# K-Diag_small-_single_small-multi.net
KiCad netlist of a schematic drawn in EAGLE
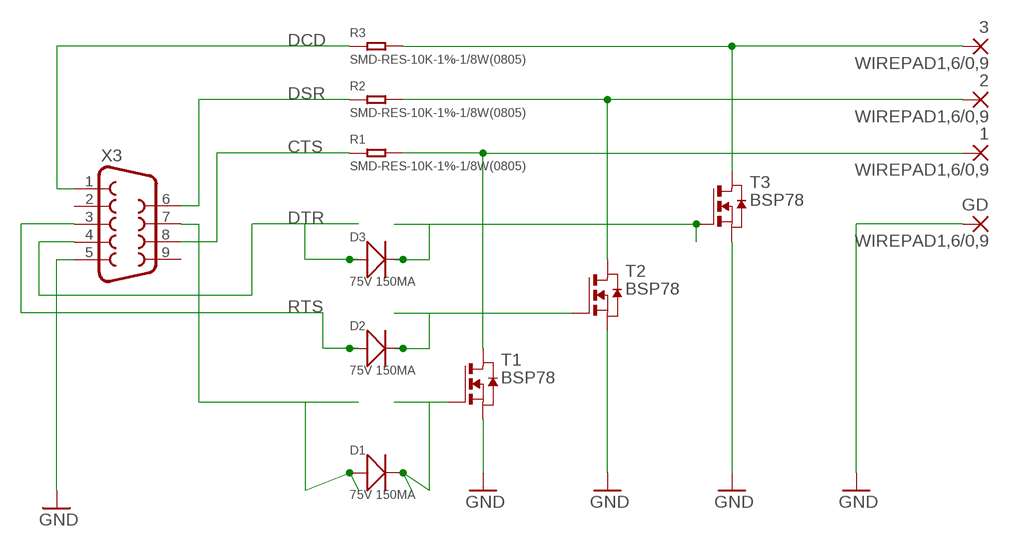
[diagram p0: schematic, sheet 1]
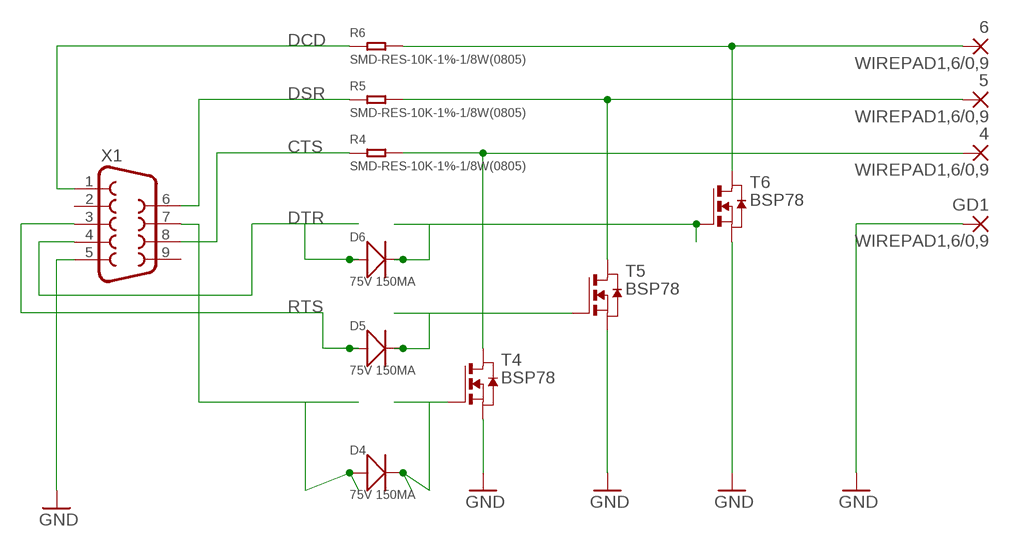
[diagram p1: schematic, sheet 2]
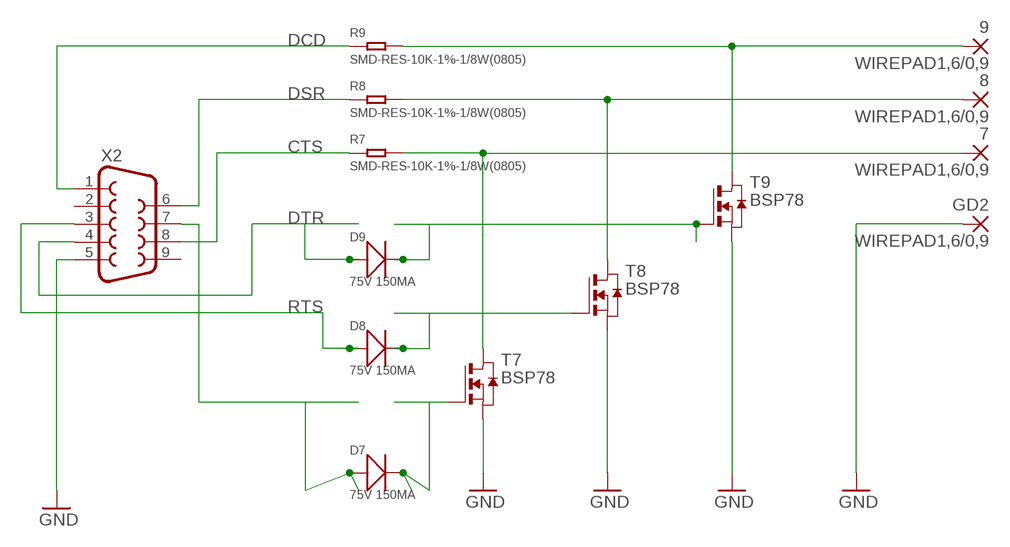
[diagram p2: schematic, sheet 3]

(export (version "E")
  (design (tool "Eeschema 10.0.6"))
  (components
    (comp (ref "7")
      (value "WIREPAD1,6/0,9")
      (footprint "eagle-import:1,6_0,9")
      (libsource (lib "eagle-import") (part "WIREPAD1,6/0,9"))
    )
    (comp (ref "8")
      (value "WIREPAD1,6/0,9")
      (footprint "eagle-import:1,6_0,9")
      (libsource (lib "eagle-import") (part "WIREPAD1,6/0,9"))
    )
    (comp (ref "9")
      (value "WIREPAD1,6/0,9")
      (footprint "eagle-import:1,6_0,9")
      (libsource (lib "eagle-import") (part "WIREPAD1,6/0,9"))
    )
    (comp (ref "D7")
      (value "75V 150MA")
      (footprint "eagle-import:LED-1206")
      (fields (field (name "MPN") "CD1206-S01575"))
      (libsource (lib "eagle-import") (part "SMD-DIODE-SWITCHING-75V-150MA(D1206)"))
    )
    (comp (ref "D8")
      (value "75V 150MA")
      (footprint "eagle-import:LED-1206")
      (fields (field (name "MPN") "CD1206-S01575"))
      (libsource (lib "eagle-import") (part "SMD-DIODE-SWITCHING-75V-150MA(D1206)"))
    )
    (comp (ref "D9")
      (value "75V 150MA")
      (footprint "eagle-import:LED-1206")
      (fields (field (name "MPN") "CD1206-S01575"))
      (libsource (lib "eagle-import") (part "SMD-DIODE-SWITCHING-75V-150MA(D1206)"))
    )
    (comp (ref "GD2")
      (value "WIREPAD1,6/0,9")
      (footprint "eagle-import:1,6_0,9")
      (libsource (lib "eagle-import") (part "WIREPAD1,6/0,9"))
    )
    (comp (ref "R7")
      (value "SMD-RES-10K-1%-1/8W(0805)")
      (footprint "eagle-import:R0805")
      (fields (field (name "MPN") "RC0805FR-0710KL"))
      (libsource (lib "eagle-import") (part "SMD-RES-10K-1%-1/8W(0805)"))
    )
    (comp (ref "R8")
      (value "SMD-RES-10K-1%-1/8W(0805)")
      (footprint "eagle-import:R0805")
      (fields (field (name "MPN") "RC0805FR-0710KL"))
      (libsource (lib "eagle-import") (part "SMD-RES-10K-1%-1/8W(0805)"))
    )
    (comp (ref "R9")
      (value "SMD-RES-10K-1%-1/8W(0805)")
      (footprint "eagle-import:R0805")
      (fields (field (name "MPN") "RC0805FR-0710KL"))
      (libsource (lib "eagle-import") (part "SMD-RES-10K-1%-1/8W(0805)"))
    )
    (comp (ref "T7")
      (value "BSP78")
      (footprint "eagle-import:SOT223")
      (libsource (lib "eagle-import") (part "NMOSSOT223"))
    )
    (comp (ref "T8")
      (value "BSP78")
      (footprint "eagle-import:SOT223")
      (libsource (lib "eagle-import") (part "NMOSSOT223"))
    )
    (comp (ref "T9")
      (value "BSP78")
      (footprint "eagle-import:SOT223")
      (libsource (lib "eagle-import") (part "NMOSSOT223"))
    )
    (comp (ref "X2")
      (value "F09D")
      (footprint "eagle-import:F09D")
      (libsource (lib "eagle-import") (part "F09D"))
    )
    (comp (ref "4")
      (value "WIREPAD1,6/0,9")
      (footprint "eagle-import:1,6_0,9")
      (libsource (lib "eagle-import") (part "WIREPAD1,6/0,9"))
    )
    (comp (ref "5")
      (value "WIREPAD1,6/0,9")
      (footprint "eagle-import:1,6_0,9")
      (libsource (lib "eagle-import") (part "WIREPAD1,6/0,9"))
    )
    (comp (ref "6")
      (value "WIREPAD1,6/0,9")
      (footprint "eagle-import:1,6_0,9")
      (libsource (lib "eagle-import") (part "WIREPAD1,6/0,9"))
    )
    (comp (ref "D4")
      (value "75V 150MA")
      (footprint "eagle-import:LED-1206")
      (fields (field (name "MPN") "CD1206-S01575"))
      (libsource (lib "eagle-import") (part "SMD-DIODE-SWITCHING-75V-150MA(D1206)"))
    )
    (comp (ref "D5")
      (value "75V 150MA")
      (footprint "eagle-import:LED-1206")
      (fields (field (name "MPN") "CD1206-S01575"))
      (libsource (lib "eagle-import") (part "SMD-DIODE-SWITCHING-75V-150MA(D1206)"))
    )
    (comp (ref "D6")
      (value "75V 150MA")
      (footprint "eagle-import:LED-1206")
      (fields (field (name "MPN") "CD1206-S01575"))
      (libsource (lib "eagle-import") (part "SMD-DIODE-SWITCHING-75V-150MA(D1206)"))
    )
    (comp (ref "GD1")
      (value "WIREPAD1,6/0,9")
      (footprint "eagle-import:1,6_0,9")
      (libsource (lib "eagle-import") (part "WIREPAD1,6/0,9"))
    )
    (comp (ref "R4")
      (value "SMD-RES-10K-1%-1/8W(0805)")
      (footprint "eagle-import:R0805")
      (fields (field (name "MPN") "RC0805FR-0710KL"))
      (libsource (lib "eagle-import") (part "SMD-RES-10K-1%-1/8W(0805)"))
    )
    (comp (ref "R5")
      (value "SMD-RES-10K-1%-1/8W(0805)")
      (footprint "eagle-import:R0805")
      (fields (field (name "MPN") "RC0805FR-0710KL"))
      (libsource (lib "eagle-import") (part "SMD-RES-10K-1%-1/8W(0805)"))
    )
    (comp (ref "R6")
      (value "SMD-RES-10K-1%-1/8W(0805)")
      (footprint "eagle-import:R0805")
      (fields (field (name "MPN") "RC0805FR-0710KL"))
      (libsource (lib "eagle-import") (part "SMD-RES-10K-1%-1/8W(0805)"))
    )
    (comp (ref "T4")
      (value "BSP78")
      (footprint "eagle-import:SOT223")
      (libsource (lib "eagle-import") (part "NMOSSOT223"))
    )
    (comp (ref "T5")
      (value "BSP78")
      (footprint "eagle-import:SOT223")
      (libsource (lib "eagle-import") (part "NMOSSOT223"))
    )
    (comp (ref "T6")
      (value "BSP78")
      (footprint "eagle-import:SOT223")
      (libsource (lib "eagle-import") (part "NMOSSOT223"))
    )
    (comp (ref "X1")
      (value "F09D")
      (footprint "eagle-import:F09D")
      (libsource (lib "eagle-import") (part "F09D"))
    )
    (comp (ref "1")
      (value "WIREPAD1,6/0,9")
      (footprint "eagle-import:1,6_0,9")
      (libsource (lib "eagle-import") (part "WIREPAD1,6/0,9"))
    )
    (comp (ref "2")
      (value "WIREPAD1,6/0,9")
      (footprint "eagle-import:1,6_0,9")
      (libsource (lib "eagle-import") (part "WIREPAD1,6/0,9"))
    )
    (comp (ref "3")
      (value "WIREPAD1,6/0,9")
      (footprint "eagle-import:1,6_0,9")
      (libsource (lib "eagle-import") (part "WIREPAD1,6/0,9"))
    )
    (comp (ref "D1")
      (value "75V 150MA")
      (footprint "eagle-import:LED-1206")
      (fields (field (name "MPN") "CD1206-S01575"))
      (libsource (lib "eagle-import") (part "SMD-DIODE-SWITCHING-75V-150MA(D1206)"))
    )
    (comp (ref "D2")
      (value "75V 150MA")
      (footprint "eagle-import:LED-1206")
      (fields (field (name "MPN") "CD1206-S01575"))
      (libsource (lib "eagle-import") (part "SMD-DIODE-SWITCHING-75V-150MA(D1206)"))
    )
    (comp (ref "D3")
      (value "75V 150MA")
      (footprint "eagle-import:LED-1206")
      (fields (field (name "MPN") "CD1206-S01575"))
      (libsource (lib "eagle-import") (part "SMD-DIODE-SWITCHING-75V-150MA(D1206)"))
    )
    (comp (ref "GD")
      (value "WIREPAD1,6/0,9")
      (footprint "eagle-import:1,6_0,9")
      (libsource (lib "eagle-import") (part "WIREPAD1,6/0,9"))
    )
    (comp (ref "R1")
      (value "SMD-RES-10K-1%-1/8W(0805)")
      (footprint "eagle-import:R0805")
      (fields (field (name "MPN") "RC0805FR-0710KL"))
      (libsource (lib "eagle-import") (part "SMD-RES-10K-1%-1/8W(0805)"))
    )
    (comp (ref "R2")
      (value "SMD-RES-10K-1%-1/8W(0805)")
      (footprint "eagle-import:R0805")
      (fields (field (name "MPN") "RC0805FR-0710KL"))
      (libsource (lib "eagle-import") (part "SMD-RES-10K-1%-1/8W(0805)"))
    )
    (comp (ref "R3")
      (value "SMD-RES-10K-1%-1/8W(0805)")
      (footprint "eagle-import:R0805")
      (fields (field (name "MPN") "RC0805FR-0710KL"))
      (libsource (lib "eagle-import") (part "SMD-RES-10K-1%-1/8W(0805)"))
    )
    (comp (ref "T1")
      (value "BSP78")
      (footprint "eagle-import:SOT223")
      (libsource (lib "eagle-import") (part "NMOSSOT223"))
    )
    (comp (ref "T2")
      (value "BSP78")
      (footprint "eagle-import:SOT223")
      (libsource (lib "eagle-import") (part "NMOSSOT223"))
    )
    (comp (ref "T3")
      (value "BSP78")
      (footprint "eagle-import:SOT223")
      (libsource (lib "eagle-import") (part "NMOSSOT223"))
    )
    (comp (ref "X3")
      (value "F09D")
      (footprint "eagle-import:F09D")
      (libsource (lib "eagle-import") (part "F09D"))
    )
  )
  (nets
    (net (code "1") (name "CTS") (class "Default")
      (node (ref "R1") (pin "1") (pinfunction "1_1") (pintype "passive"))
      (node (ref "R4") (pin "1") (pinfunction "1_1") (pintype "passive"))
      (node (ref "R7") (pin "1") (pinfunction "1_1") (pintype "passive"))
      (node (ref "X1") (pin "8") (pinfunction "8_8") (pintype "passive"))
      (node (ref "X2") (pin "8") (pinfunction "8_8") (pintype "passive"))
      (node (ref "X3") (pin "8") (pinfunction "8_8") (pintype "passive"))
    )
    (net (code "2") (name "DCD") (class "Default")
      (node (ref "R3") (pin "1") (pinfunction "1_1") (pintype "passive"))
      (node (ref "R6") (pin "1") (pinfunction "1_1") (pintype "passive"))
      (node (ref "R9") (pin "1") (pinfunction "1_1") (pintype "passive"))
      (node (ref "X1") (pin "1") (pinfunction "1_1") (pintype "passive"))
      (node (ref "X2") (pin "1") (pinfunction "1_1") (pintype "passive"))
      (node (ref "X3") (pin "1") (pinfunction "1_1") (pintype "passive"))
    )
    (net (code "3") (name "DSR") (class "Default")
      (node (ref "R2") (pin "1") (pinfunction "1_1") (pintype "passive"))
      (node (ref "R5") (pin "1") (pinfunction "1_1") (pintype "passive"))
      (node (ref "R8") (pin "1") (pinfunction "1_1") (pintype "passive"))
      (node (ref "X1") (pin "6") (pinfunction "6_6") (pintype "passive"))
      (node (ref "X2") (pin "6") (pinfunction "6_6") (pintype "passive"))
      (node (ref "X3") (pin "6") (pinfunction "6_6") (pintype "passive"))
    )
    (net (code "4") (name "DTR") (class "Default")
      (node (ref "D3") (pin "+") (pinfunction "+_+") (pintype "passive"))
      (node (ref "D6") (pin "+") (pinfunction "+_+") (pintype "passive"))
      (node (ref "D9") (pin "+") (pinfunction "+_+") (pintype "passive"))
      (node (ref "X1") (pin "4") (pinfunction "4_4") (pintype "passive"))
      (node (ref "X2") (pin "4") (pinfunction "4_4") (pintype "passive"))
      (node (ref "X3") (pin "4") (pinfunction "4_4") (pintype "passive"))
    )
    (net (code "5") (name "GND") (class "Default")
      (node (ref "GD") (pin "1") (pinfunction "P_1") (pintype "passive"))
      (node (ref "GD1") (pin "1") (pinfunction "P_1") (pintype "passive"))
      (node (ref "GD2") (pin "1") (pinfunction "P_1") (pintype "passive"))
      (node (ref "T1") (pin "3") (pinfunction "S_3") (pintype "passive"))
      (node (ref "T2") (pin "3") (pinfunction "S_3") (pintype "passive"))
      (node (ref "T3") (pin "3") (pinfunction "S_3") (pintype "passive"))
      (node (ref "T4") (pin "3") (pinfunction "S_3") (pintype "passive"))
      (node (ref "T5") (pin "3") (pinfunction "S_3") (pintype "passive"))
      (node (ref "T6") (pin "3") (pinfunction "S_3") (pintype "passive"))
      (node (ref "T7") (pin "3") (pinfunction "S_3") (pintype "passive"))
      (node (ref "T8") (pin "3") (pinfunction "S_3") (pintype "passive"))
      (node (ref "T9") (pin "3") (pinfunction "S_3") (pintype "passive"))
      (node (ref "X1") (pin "5") (pinfunction "5_5") (pintype "passive"))
      (node (ref "X2") (pin "5") (pinfunction "5_5") (pintype "passive"))
      (node (ref "X3") (pin "5") (pinfunction "5_5") (pintype "passive"))
    )
    (net (code "6") (name "Net-(1-P)") (class "Default")
      (node (ref "1") (pin "1") (pinfunction "P_1") (pintype "passive"))
      (node (ref "R1") (pin "2") (pinfunction "2_2") (pintype "passive"))
      (node (ref "T1") (pin "2") (pinfunction "D_2") (pintype "passive"))
      (node (ref "T1") (pin "4") (pinfunction "D_4") (pintype "passive"))
    )
    (net (code "7") (name "Net-(2-P)") (class "Default")
      (node (ref "2") (pin "1") (pinfunction "P_1") (pintype "passive"))
      (node (ref "R2") (pin "2") (pinfunction "2_2") (pintype "passive"))
      (node (ref "T2") (pin "2") (pinfunction "D_2") (pintype "passive"))
      (node (ref "T2") (pin "4") (pinfunction "D_4") (pintype "passive"))
    )
    (net (code "8") (name "Net-(3-P)") (class "Default")
      (node (ref "3") (pin "1") (pinfunction "P_1") (pintype "passive"))
      (node (ref "R3") (pin "2") (pinfunction "2_2") (pintype "passive"))
      (node (ref "T3") (pin "2") (pinfunction "D_2") (pintype "passive"))
      (node (ref "T3") (pin "4") (pinfunction "D_4") (pintype "passive"))
    )
    (net (code "9") (name "Net-(4-P)") (class "Default")
      (node (ref "4") (pin "1") (pinfunction "P_1") (pintype "passive"))
      (node (ref "R4") (pin "2") (pinfunction "2_2") (pintype "passive"))
      (node (ref "T4") (pin "2") (pinfunction "D_2") (pintype "passive"))
      (node (ref "T4") (pin "4") (pinfunction "D_4") (pintype "passive"))
    )
    (net (code "10") (name "Net-(5-P)") (class "Default")
      (node (ref "5") (pin "1") (pinfunction "P_1") (pintype "passive"))
      (node (ref "R5") (pin "2") (pinfunction "2_2") (pintype "passive"))
      (node (ref "T5") (pin "2") (pinfunction "D_2") (pintype "passive"))
      (node (ref "T5") (pin "4") (pinfunction "D_4") (pintype "passive"))
    )
    (net (code "11") (name "Net-(6-P)") (class "Default")
      (node (ref "6") (pin "1") (pinfunction "P_1") (pintype "passive"))
      (node (ref "R6") (pin "2") (pinfunction "2_2") (pintype "passive"))
      (node (ref "T6") (pin "2") (pinfunction "D_2") (pintype "passive"))
      (node (ref "T6") (pin "4") (pinfunction "D_4") (pintype "passive"))
    )
    (net (code "12") (name "Net-(7-P)") (class "Default")
      (node (ref "7") (pin "1") (pinfunction "P_1") (pintype "passive"))
      (node (ref "R7") (pin "2") (pinfunction "2_2") (pintype "passive"))
      (node (ref "T7") (pin "2") (pinfunction "D_2") (pintype "passive"))
      (node (ref "T7") (pin "4") (pinfunction "D_4") (pintype "passive"))
    )
    (net (code "13") (name "Net-(8-P)") (class "Default")
      (node (ref "8") (pin "1") (pinfunction "P_1") (pintype "passive"))
      (node (ref "R8") (pin "2") (pinfunction "2_2") (pintype "passive"))
      (node (ref "T8") (pin "2") (pinfunction "D_2") (pintype "passive"))
      (node (ref "T8") (pin "4") (pinfunction "D_4") (pintype "passive"))
    )
    (net (code "14") (name "Net-(9-P)") (class "Default")
      (node (ref "9") (pin "1") (pinfunction "P_1") (pintype "passive"))
      (node (ref "R9") (pin "2") (pinfunction "2_2") (pintype "passive"))
      (node (ref "T9") (pin "2") (pinfunction "D_2") (pintype "passive"))
      (node (ref "T9") (pin "4") (pinfunction "D_4") (pintype "passive"))
    )
    (net (code "15") (name "Net-(D1-Pad+)") (class "Default")
      (node (ref "D1") (pin "+") (pinfunction "+_+") (pintype "passive"))
      (node (ref "X3") (pin "7") (pinfunction "7_7") (pintype "passive"))
    )
    (net (code "16") (name "Net-(D4-Pad+)") (class "Default")
      (node (ref "D4") (pin "+") (pinfunction "+_+") (pintype "passive"))
      (node (ref "X1") (pin "7") (pinfunction "7_7") (pintype "passive"))
    )
    (net (code "17") (name "Net-(D7-Pad+)") (class "Default")
      (node (ref "D7") (pin "+") (pinfunction "+_+") (pintype "passive"))
      (node (ref "X2") (pin "7") (pinfunction "7_7") (pintype "passive"))
    )
    (net (code "18") (name "Net-(T1-G)") (class "Default")
      (node (ref "D1") (pin "-") (pinfunction "-_-") (pintype "passive"))
      (node (ref "T1") (pin "1") (pinfunction "G_1") (pintype "passive"))
    )
    (net (code "19") (name "Net-(T2-G)") (class "Default")
      (node (ref "D2") (pin "-") (pinfunction "-_-") (pintype "passive"))
      (node (ref "T2") (pin "1") (pinfunction "G_1") (pintype "passive"))
    )
    (net (code "20") (name "Net-(T3-G)") (class "Default")
      (node (ref "D3") (pin "-") (pinfunction "-_-") (pintype "passive"))
      (node (ref "T3") (pin "1") (pinfunction "G_1") (pintype "passive"))
    )
    (net (code "21") (name "Net-(T4-G)") (class "Default")
      (node (ref "D4") (pin "-") (pinfunction "-_-") (pintype "passive"))
      (node (ref "T4") (pin "1") (pinfunction "G_1") (pintype "passive"))
    )
    (net (code "22") (name "Net-(T5-G)") (class "Default")
      (node (ref "D5") (pin "-") (pinfunction "-_-") (pintype "passive"))
      (node (ref "T5") (pin "1") (pinfunction "G_1") (pintype "passive"))
    )
    (net (code "23") (name "Net-(T6-G)") (class "Default")
      (node (ref "D6") (pin "-") (pinfunction "-_-") (pintype "passive"))
      (node (ref "T6") (pin "1") (pinfunction "G_1") (pintype "passive"))
    )
    (net (code "24") (name "Net-(T7-G)") (class "Default")
      (node (ref "D7") (pin "-") (pinfunction "-_-") (pintype "passive"))
      (node (ref "T7") (pin "1") (pinfunction "G_1") (pintype "passive"))
    )
    (net (code "25") (name "Net-(T8-G)") (class "Default")
      (node (ref "D8") (pin "-") (pinfunction "-_-") (pintype "passive"))
      (node (ref "T8") (pin "1") (pinfunction "G_1") (pintype "passive"))
    )
    (net (code "26") (name "Net-(T9-G)") (class "Default")
      (node (ref "D9") (pin "-") (pinfunction "-_-") (pintype "passive"))
      (node (ref "T9") (pin "1") (pinfunction "G_1") (pintype "passive"))
    )
    (net (code "27") (name "RTS") (class "Default")
      (node (ref "D2") (pin "+") (pinfunction "+_+") (pintype "passive"))
      (node (ref "D5") (pin "+") (pinfunction "+_+") (pintype "passive"))
      (node (ref "D8") (pin "+") (pinfunction "+_+") (pintype "passive"))
      (node (ref "X1") (pin "3") (pinfunction "3_3") (pintype "passive"))
      (node (ref "X2") (pin "3") (pinfunction "3_3") (pintype "passive"))
      (node (ref "X3") (pin "3") (pinfunction "3_3") (pintype "passive"))
    )
    (net (code "28") (name "unconnected-(X1-Pad2)") (class "Default")
      (node (ref "X1") (pin "2") (pinfunction "2_2") (pintype "passive"))
    )
    (net (code "29") (name "unconnected-(X1-Pad9)") (class "Default")
      (node (ref "X1") (pin "9") (pinfunction "9_9") (pintype "passive"))
    )
    (net (code "30") (name "unconnected-(X2-Pad2)") (class "Default")
      (node (ref "X2") (pin "2") (pinfunction "2_2") (pintype "passive"))
    )
    (net (code "31") (name "unconnected-(X2-Pad9)") (class "Default")
      (node (ref "X2") (pin "9") (pinfunction "9_9") (pintype "passive"))
    )
    (net (code "32") (name "unconnected-(X3-Pad2)") (class "Default")
      (node (ref "X3") (pin "2") (pinfunction "2_2") (pintype "passive"))
    )
    (net (code "33") (name "unconnected-(X3-Pad9)") (class "Default")
      (node (ref "X3") (pin "9") (pinfunction "9_9") (pintype "passive"))
    )
  )
)
